# main.net
KiCad netlist of a schematic drawn in EAGLE
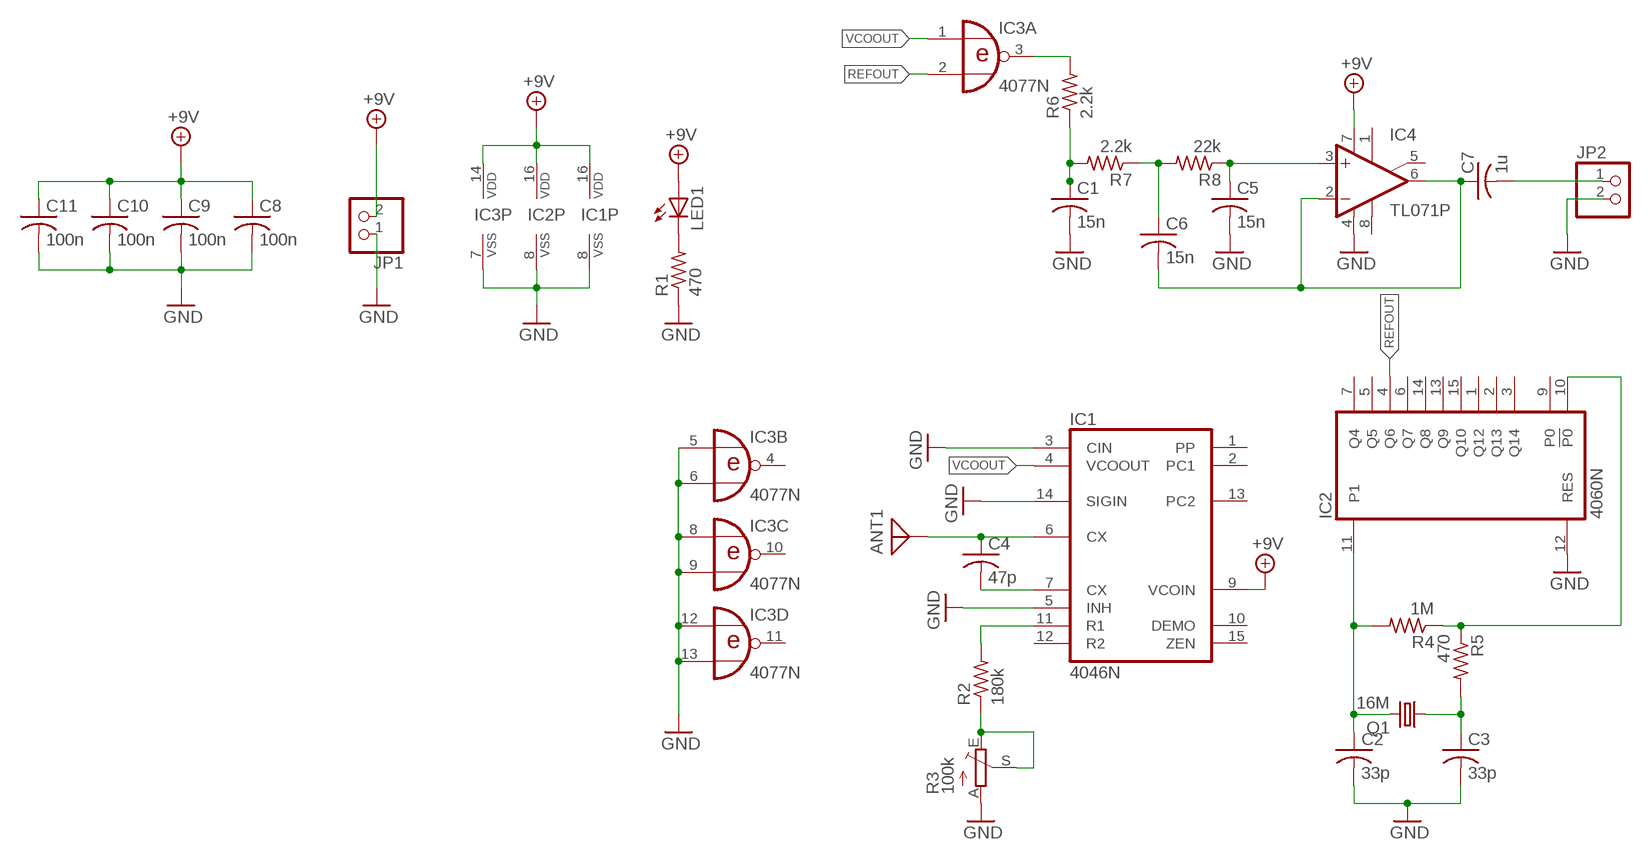
[diagram p0: schematic, sheet 1]

(export (version "E")
  (design (tool "Eeschema 10.0.6"))
  (components
    (comp (ref "ANT1")
      (value "ANTENNA")
      (footprint "eagle-import:PAD-01")
      (libsource (lib "eagle-import") (part "ANTENNA"))
    )
    (comp (ref "C1")
      (value "15n")
      (footprint "eagle-import:C050-025X075")
      (libsource (lib "eagle-import") (part "C-US050-025X075"))
    )
    (comp (ref "C2")
      (value "33p")
      (footprint "eagle-import:C050-025X075")
      (libsource (lib "eagle-import") (part "C-US050-025X075"))
    )
    (comp (ref "C3")
      (value "33p")
      (footprint "eagle-import:C050-025X075")
      (libsource (lib "eagle-import") (part "C-US050-025X075"))
    )
    (comp (ref "C4")
      (value "47p")
      (footprint "eagle-import:C050-025X075")
      (libsource (lib "eagle-import") (part "C-US050-025X075"))
    )
    (comp (ref "C5")
      (value "15n")
      (footprint "eagle-import:C050-025X075")
      (libsource (lib "eagle-import") (part "C-US050-025X075"))
    )
    (comp (ref "C6")
      (value "15n")
      (footprint "eagle-import:C050-025X075")
      (libsource (lib "eagle-import") (part "C-US050-025X075"))
    )
    (comp (ref "C7")
      (value "1u")
      (footprint "eagle-import:C050-025X075")
      (libsource (lib "eagle-import") (part "C-US050-025X075"))
    )
    (comp (ref "C8")
      (value "100n")
      (footprint "eagle-import:C050-025X075")
      (libsource (lib "eagle-import") (part "C-US050-025X075"))
    )
    (comp (ref "C9")
      (value "100n")
      (footprint "eagle-import:C050-025X075")
      (libsource (lib "eagle-import") (part "C-US050-025X075"))
    )
    (comp (ref "C10")
      (value "100n")
      (footprint "eagle-import:C050-025X075")
      (libsource (lib "eagle-import") (part "C-US050-025X075"))
    )
    (comp (ref "C11")
      (value "100n")
      (footprint "eagle-import:C050-025X075")
      (libsource (lib "eagle-import") (part "C-US050-025X075"))
    )
    (comp (ref "IC1")
      (value "4046N")
      (footprint "eagle-import:DIL16")
      (libsource (lib "eagle-import") (part "4046N"))
    )
    (comp (ref "IC2")
      (value "4060N")
      (footprint "eagle-import:DIL16")
      (libsource (lib "eagle-import") (part "4060N"))
    )
    (comp (ref "IC3")
      (value "4077N")
      (footprint "eagle-import:DIL14")
      (libsource (lib "eagle-import") (part "4077N"))
    )
    (comp (ref "IC4")
      (value "TL071P")
      (footprint "eagle-import:DIL08")
      (libsource (lib "eagle-import") (part "TL071P"))
    )
    (comp (ref "JP1")
      (value "PINHD-1X2")
      (footprint "eagle-import:1X02")
      (libsource (lib "eagle-import") (part "PINHD-1X2"))
    )
    (comp (ref "JP2")
      (value "PINHD-1X2")
      (footprint "eagle-import:1X02")
      (libsource (lib "eagle-import") (part "PINHD-1X2"))
    )
    (comp (ref "LED1")
      (value "LED3MM")
      (footprint "eagle-import:LED3MM")
      (libsource (lib "eagle-import") (part "LED3MM"))
    )
    (comp (ref "Q1")
      (value "16M")
      (footprint "eagle-import:HC49_S")
      (libsource (lib "eagle-import") (part "CRYSTALHC49S"))
    )
    (comp (ref "R1")
      (value "470")
      (footprint "eagle-import:0204_7")
      (libsource (lib "eagle-import") (part "R-US_0204/7"))
    )
    (comp (ref "R2")
      (value "180k")
      (footprint "eagle-import:0207_10")
      (libsource (lib "eagle-import") (part "R-US_0207/10"))
    )
    (comp (ref "R3")
      (value "100k")
      (footprint "eagle-import:RJ9W")
      (libsource (lib "eagle-import") (part "TRIM_EU-RJ9W"))
    )
    (comp (ref "R4")
      (value "1M")
      (footprint "eagle-import:0204_7")
      (libsource (lib "eagle-import") (part "R-US_0204/7"))
    )
    (comp (ref "R5")
      (value "470")
      (footprint "eagle-import:0204_7")
      (libsource (lib "eagle-import") (part "R-US_0204/7"))
    )
    (comp (ref "R6")
      (value "2.2k")
      (footprint "eagle-import:0204_7")
      (libsource (lib "eagle-import") (part "R-US_0204/7"))
    )
    (comp (ref "R7")
      (value "2.2k")
      (footprint "eagle-import:0204_7")
      (libsource (lib "eagle-import") (part "R-US_0204/7"))
    )
    (comp (ref "R8")
      (value "22k")
      (footprint "eagle-import:0204_7")
      (libsource (lib "eagle-import") (part "R-US_0204/7"))
    )
  )
  (nets
    (net (code "1") (name "+9V") (class "Default")
      (node (ref "C10") (pin "1") (pinfunction "1_1") (pintype "passive"))
      (node (ref "C11") (pin "1") (pinfunction "1_1") (pintype "passive"))
      (node (ref "C8") (pin "1") (pinfunction "1_1") (pintype "passive"))
      (node (ref "C9") (pin "1") (pinfunction "1_1") (pintype "passive"))
      (node (ref "IC1") (pin "16") (pinfunction "VDD_16") (pintype "power_in"))
      (node (ref "IC1") (pin "9") (pinfunction "VCOIN_9") (pintype "input"))
      (node (ref "IC2") (pin "16") (pinfunction "VDD_16") (pintype "power_in"))
      (node (ref "IC3") (pin "14") (pinfunction "VDD_14") (pintype "power_in"))
      (node (ref "IC4") (pin "7") (pinfunction "V+_7") (pintype "power_in"))
      (node (ref "JP1") (pin "2") (pinfunction "2_2") (pintype "passive"))
      (node (ref "LED1") (pin "A") (pinfunction "A_A") (pintype "passive"))
    )
    (net (code "2") (name "GND") (class "Default")
      (node (ref "C1") (pin "2") (pinfunction "2_2") (pintype "passive"))
      (node (ref "C10") (pin "2") (pinfunction "2_2") (pintype "passive"))
      (node (ref "C11") (pin "2") (pinfunction "2_2") (pintype "passive"))
      (node (ref "C2") (pin "2") (pinfunction "2_2") (pintype "passive"))
      (node (ref "C3") (pin "2") (pinfunction "2_2") (pintype "passive"))
      (node (ref "C5") (pin "2") (pinfunction "2_2") (pintype "passive"))
      (node (ref "C8") (pin "2") (pinfunction "2_2") (pintype "passive"))
      (node (ref "C9") (pin "2") (pinfunction "2_2") (pintype "passive"))
      (node (ref "IC1") (pin "14") (pinfunction "SIGIN_14") (pintype "input"))
      (node (ref "IC1") (pin "3") (pinfunction "CIN_3") (pintype "input"))
      (node (ref "IC1") (pin "5") (pinfunction "INH_5") (pintype "input"))
      (node (ref "IC1") (pin "8") (pinfunction "VSS_8") (pintype "power_in"))
      (node (ref "IC2") (pin "12") (pinfunction "RES_12") (pintype "input"))
      (node (ref "IC2") (pin "8") (pinfunction "VSS_8") (pintype "power_in"))
      (node (ref "IC3") (pin "12") (pinfunction "I0_12") (pintype "input"))
      (node (ref "IC3") (pin "13") (pinfunction "I1_13") (pintype "input"))
      (node (ref "IC3") (pin "5") (pinfunction "I0_5") (pintype "input"))
      (node (ref "IC3") (pin "6") (pinfunction "I1_6") (pintype "input"))
      (node (ref "IC3") (pin "7") (pinfunction "VSS_7") (pintype "power_in"))
      (node (ref "IC3") (pin "8") (pinfunction "I0_8") (pintype "input"))
      (node (ref "IC3") (pin "9") (pinfunction "I1_9") (pintype "input"))
      (node (ref "IC4") (pin "4") (pinfunction "V-_4") (pintype "power_in"))
      (node (ref "JP1") (pin "1") (pinfunction "1_1") (pintype "passive"))
      (node (ref "JP2") (pin "2") (pinfunction "2_2") (pintype "passive"))
      (node (ref "R1") (pin "1") (pinfunction "1_1") (pintype "passive"))
      (node (ref "R3") (pin "A") (pinfunction "A_A") (pintype "passive"))
    )
    (net (code "3") (name "Net-(ANT1-Pad1)") (class "Default")
      (node (ref "ANT1") (pin "1") (pinfunction "1_1") (pintype "output"))
      (node (ref "C4") (pin "1") (pinfunction "1_1") (pintype "passive"))
      (node (ref "IC1") (pin "6") (pinfunction "CX_6") (pintype "input"))
    )
    (net (code "4") (name "Net-(C1-Pad1)") (class "Default")
      (node (ref "C1") (pin "1") (pinfunction "1_1") (pintype "passive"))
      (node (ref "R6") (pin "1") (pinfunction "1_1") (pintype "passive"))
      (node (ref "R7") (pin "2") (pinfunction "2_2") (pintype "passive"))
    )
    (net (code "5") (name "Net-(C3-Pad1)") (class "Default")
      (node (ref "C3") (pin "1") (pinfunction "1_1") (pintype "passive"))
      (node (ref "Q1") (pin "1") (pinfunction "1_1") (pintype "passive"))
      (node (ref "R5") (pin "2") (pinfunction "2_2") (pintype "passive"))
    )
    (net (code "6") (name "Net-(C4-Pad2)") (class "Default")
      (node (ref "C4") (pin "2") (pinfunction "2_2") (pintype "passive"))
      (node (ref "IC1") (pin "7") (pinfunction "CX_7") (pintype "input"))
    )
    (net (code "7") (name "Net-(C6-Pad1)") (class "Default")
      (node (ref "C6") (pin "1") (pinfunction "1_1") (pintype "passive"))
      (node (ref "R7") (pin "1") (pinfunction "1_1") (pintype "passive"))
      (node (ref "R8") (pin "2") (pinfunction "2_2") (pintype "passive"))
    )
    (net (code "8") (name "Net-(C7-Pad2)") (class "Default")
      (node (ref "C7") (pin "2") (pinfunction "2_2") (pintype "passive"))
      (node (ref "JP2") (pin "1") (pinfunction "1_1") (pintype "passive"))
    )
    (net (code "9") (name "Net-(IC1A-R1)") (class "Default")
      (node (ref "IC1") (pin "11") (pinfunction "R1_11") (pintype "input"))
      (node (ref "R2") (pin "2") (pinfunction "2_2") (pintype "passive"))
    )
    (net (code "10") (name "Net-(IC2A-P1)") (class "Default")
      (node (ref "C2") (pin "1") (pinfunction "1_1") (pintype "passive"))
      (node (ref "IC2") (pin "11") (pinfunction "P1_11") (pintype "input"))
      (node (ref "Q1") (pin "2") (pinfunction "2_2") (pintype "passive"))
      (node (ref "R4") (pin "2") (pinfunction "2_2") (pintype "passive"))
    )
    (net (code "11") (name "Net-(IC2A-~{P0})") (class "Default")
      (node (ref "IC2") (pin "10") (pinfunction "~{P0}_10") (pintype "output"))
      (node (ref "R4") (pin "1") (pinfunction "1_1") (pintype "passive"))
      (node (ref "R5") (pin "1") (pinfunction "1_1") (pintype "passive"))
    )
    (net (code "12") (name "Net-(IC3A-O)") (class "Default")
      (node (ref "IC3") (pin "3") (pinfunction "O_3") (pintype "output"))
      (node (ref "R6") (pin "2") (pinfunction "2_2") (pintype "passive"))
    )
    (net (code "13") (name "Net-(IC4-+IN)") (class "Default")
      (node (ref "C5") (pin "1") (pinfunction "1_1") (pintype "passive"))
      (node (ref "IC4") (pin "3") (pinfunction "+IN_3") (pintype "input"))
      (node (ref "R8") (pin "1") (pinfunction "1_1") (pintype "passive"))
    )
    (net (code "14") (name "Net-(IC4--IN)") (class "Default")
      (node (ref "C6") (pin "2") (pinfunction "2_2") (pintype "passive"))
      (node (ref "C7") (pin "1") (pinfunction "1_1") (pintype "passive"))
      (node (ref "IC4") (pin "2") (pinfunction "-IN_2") (pintype "input"))
      (node (ref "IC4") (pin "6") (pinfunction "OUT_6") (pintype "output"))
    )
    (net (code "15") (name "Net-(LED1-C)") (class "Default")
      (node (ref "LED1") (pin "K") (pinfunction "C_K") (pintype "passive"))
      (node (ref "R1") (pin "2") (pinfunction "2_2") (pintype "passive"))
    )
    (net (code "16") (name "Net-(R2-Pad1)") (class "Default")
      (node (ref "R2") (pin "1") (pinfunction "1_1") (pintype "passive"))
      (node (ref "R3") (pin "E") (pinfunction "E_E") (pintype "passive"))
      (node (ref "R3") (pin "S") (pinfunction "S_S") (pintype "passive"))
    )
    (net (code "17") (name "REFOUT") (class "Default")
      (node (ref "IC2") (pin "4") (pinfunction "Q6_4") (pintype "output"))
      (node (ref "IC3") (pin "2") (pinfunction "I1_2") (pintype "input"))
    )
    (net (code "18") (name "VCOOUT") (class "Default")
      (node (ref "IC1") (pin "4") (pinfunction "VCOOUT_4") (pintype "output"))
      (node (ref "IC3") (pin "1") (pinfunction "I0_1") (pintype "input"))
    )
    (net (code "19") (name "unconnected-(IC1A-DEMO-Pad10)") (class "Default")
      (node (ref "IC1") (pin "10") (pinfunction "DEMO_10") (pintype "output"))
    )
    (net (code "20") (name "unconnected-(IC1A-PC1-Pad2)") (class "Default")
      (node (ref "IC1") (pin "2") (pinfunction "PC1_2") (pintype "output"))
    )
    (net (code "21") (name "unconnected-(IC1A-PC2-Pad13)") (class "Default")
      (node (ref "IC1") (pin "13") (pinfunction "PC2_13") (pintype "output"))
    )
    (net (code "22") (name "unconnected-(IC1A-PP-Pad1)") (class "Default")
      (node (ref "IC1") (pin "1") (pinfunction "PP_1") (pintype "output"))
    )
    (net (code "23") (name "unconnected-(IC1A-R2-Pad12)") (class "Default")
      (node (ref "IC1") (pin "12") (pinfunction "R2_12") (pintype "input"))
    )
    (net (code "24") (name "unconnected-(IC1A-ZEN-Pad15)") (class "Default")
      (node (ref "IC1") (pin "15") (pinfunction "ZEN_15") (pintype "input"))
    )
    (net (code "25") (name "unconnected-(IC2A-P0-Pad9)") (class "Default")
      (node (ref "IC2") (pin "9") (pinfunction "P0_9") (pintype "output"))
    )
    (net (code "26") (name "unconnected-(IC2A-Q4-Pad7)") (class "Default")
      (node (ref "IC2") (pin "7") (pinfunction "Q4_7") (pintype "output"))
    )
    (net (code "27") (name "unconnected-(IC2A-Q5-Pad5)") (class "Default")
      (node (ref "IC2") (pin "5") (pinfunction "Q5_5") (pintype "output"))
    )
    (net (code "28") (name "unconnected-(IC2A-Q7-Pad6)") (class "Default")
      (node (ref "IC2") (pin "6") (pinfunction "Q7_6") (pintype "output"))
    )
    (net (code "29") (name "unconnected-(IC2A-Q8-Pad14)") (class "Default")
      (node (ref "IC2") (pin "14") (pinfunction "Q8_14") (pintype "output"))
    )
    (net (code "30") (name "unconnected-(IC2A-Q9-Pad13)") (class "Default")
      (node (ref "IC2") (pin "13") (pinfunction "Q9_13") (pintype "output"))
    )
    (net (code "31") (name "unconnected-(IC2A-Q10-Pad15)") (class "Default")
      (node (ref "IC2") (pin "15") (pinfunction "Q10_15") (pintype "output"))
    )
    (net (code "32") (name "unconnected-(IC2A-Q12-Pad1)") (class "Default")
      (node (ref "IC2") (pin "1") (pinfunction "Q12_1") (pintype "output"))
    )
    (net (code "33") (name "unconnected-(IC2A-Q13-Pad2)") (class "Default")
      (node (ref "IC2") (pin "2") (pinfunction "Q13_2") (pintype "output"))
    )
    (net (code "34") (name "unconnected-(IC2A-Q14-Pad3)") (class "Default")
      (node (ref "IC2") (pin "3") (pinfunction "Q14_3") (pintype "output"))
    )
    (net (code "35") (name "unconnected-(IC3B-O-Pad4)") (class "Default")
      (node (ref "IC3") (pin "4") (pinfunction "O_4") (pintype "output"))
    )
    (net (code "36") (name "unconnected-(IC3C-O-Pad10)") (class "Default")
      (node (ref "IC3") (pin "10") (pinfunction "O_10") (pintype "output"))
    )
    (net (code "37") (name "unconnected-(IC3D-O-Pad11)") (class "Default")
      (node (ref "IC3") (pin "11") (pinfunction "O_11") (pintype "output"))
    )
    (net (code "38") (name "unconnected-(IC4-ON1-Pad1)") (class "Default")
      (node (ref "IC4") (pin "1") (pinfunction "ON1_1") (pintype "passive"))
    )
    (net (code "39") (name "unconnected-(IC4-ON2-Pad5)") (class "Default")
      (node (ref "IC4") (pin "5") (pinfunction "ON2_5") (pintype "passive"))
    )
    (net (code "40") (name "unconnected-(IC4-OPT-Pad8)") (class "Default")
      (node (ref "IC4") (pin "8") (pinfunction "OPT_8") (pintype "passive"))
    )
  )
)
